# SCH_07_Output.net
KiCad netlist of a schematic drawn in Altium Designer
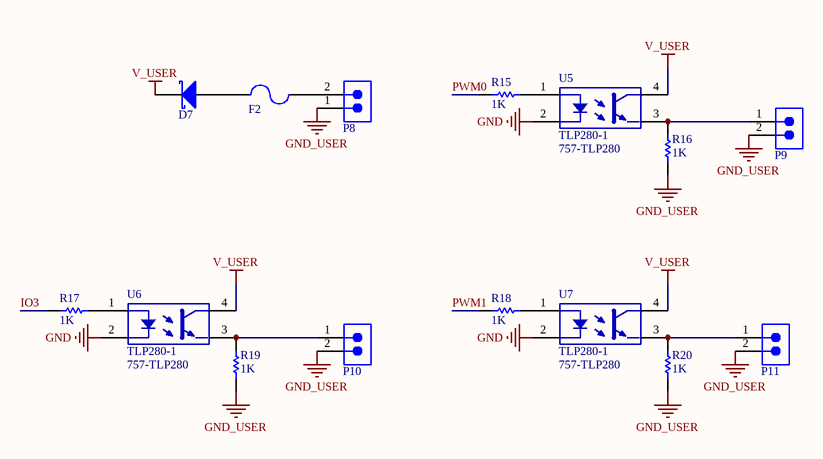
[diagram p0: SCH_07_Output.SchDoc]

(export (version "E")
  (design (tool "Eeschema 10.0.6"))
  (components
    (comp (ref "D7")
      (value "D Schottky")
      (footprint "SS34")
      (description "Schottky Diode")
      (fields (field (name "PUBLISHER") "Altium Limited"))
      (libsource (lib "PIF_Library") (part "D Schottky"))
    )
    (comp (ref "F2") (value "Fuse") (footprint "FUSE SMD") (libsource (lib "PIF_Library") (part "Fuse")))
    (comp (ref "P8")
      (value "691312510002")
      (footprint "691312510002")
      (description "WR-TBL Series 312 Open Horizontal PCB Header, THT, pitch 5.08mm, 2p")
      (fields (field (name "MANUFACTURER") "Wurth Elektronik"))
      (libsource (lib "Altium_WR-TBL (rev22b)") (part "691312510002"))
    )
    (comp (ref "P9")
      (value "691312510002")
      (footprint "691312510002")
      (description "WR-TBL Series 312 Open Horizontal PCB Header, THT, pitch 5.08mm, 2p")
      (fields (field (name "MANUFACTURER") "Wurth Elektronik"))
      (libsource (lib "Altium_WR-TBL (rev22b)") (part "691312510002"))
    )
    (comp (ref "P10")
      (value "691312510002")
      (footprint "691312510002")
      (description "WR-TBL Series 312 Open Horizontal PCB Header, THT, pitch 5.08mm, 2p")
      (fields (field (name "MANUFACTURER") "Wurth Elektronik"))
      (libsource (lib "Altium_WR-TBL (rev22b)") (part "691312510002"))
    )
    (comp (ref "P11")
      (value "691312510002")
      (footprint "691312510002")
      (description "WR-TBL Series 312 Open Horizontal PCB Header, THT, pitch 5.08mm, 2p")
      (fields (field (name "MANUFACTURER") "Wurth Elektronik"))
      (libsource (lib "Altium_WR-TBL (rev22b)") (part "691312510002"))
    )
    (comp (ref "R15")
      (value "1K")
      (footprint "RES-SM-0603")
      (description "Resistor")
      (fields (field (name "Comment") "RESISTOR SMD"))
      (libsource (lib "PIF_Library") (part "RESISTOR SMD"))
    )
    (comp (ref "R16")
      (value "1K")
      (footprint "RES-SM-0603")
      (description "Resistor")
      (fields (field (name "Comment") "RESISTOR SMD"))
      (libsource (lib "PIF_Library") (part "RESISTOR SMD"))
    )
    (comp (ref "R17")
      (value "1K")
      (footprint "RES-SM-0603")
      (description "Resistor")
      (fields (field (name "Comment") "RESISTOR SMD"))
      (libsource (lib "PIF_Library") (part "RESISTOR SMD"))
    )
    (comp (ref "R18")
      (value "1K")
      (footprint "RES-SM-0603")
      (description "Resistor")
      (fields (field (name "Comment") "RESISTOR SMD"))
      (libsource (lib "PIF_Library") (part "RESISTOR SMD"))
    )
    (comp (ref "R19")
      (value "1K")
      (footprint "RES-SM-0603")
      (description "Resistor")
      (fields (field (name "Comment") "RESISTOR SMD"))
      (libsource (lib "PIF_Library") (part "RESISTOR SMD"))
    )
    (comp (ref "R20")
      (value "1K")
      (footprint "RES-SM-0603")
      (description "Resistor")
      (fields (field (name "Comment") "RESISTOR SMD"))
      (libsource (lib "PIF_Library") (part "RESISTOR SMD"))
    )
    (comp (ref "U5")
      (value "TLP280-1")
      (footprint "SOIC127P700X240-4N")
      (description "Transistor Output Optocouplers 80Vceo 2500Vrms AC input")
      (fields (field (name "SUPPLIER PART NUMBER 1") "757-TLP280"))
      (libsource (lib "Huy_Lib") (part "TLP280-1"))
    )
    (comp (ref "U6")
      (value "TLP280-1")
      (footprint "SOIC127P700X240-4N")
      (description "Transistor Output Optocouplers 80Vceo 2500Vrms AC input")
      (fields (field (name "SUPPLIER PART NUMBER 1") "757-TLP280"))
      (libsource (lib "Huy_Lib") (part "TLP280-1"))
    )
    (comp (ref "U7")
      (value "TLP280-1")
      (footprint "SOIC127P700X240-4N")
      (description "Transistor Output Optocouplers 80Vceo 2500Vrms AC input")
      (fields (field (name "SUPPLIER PART NUMBER 1") "757-TLP280"))
      (libsource (lib "Huy_Lib") (part "TLP280-1"))
    )
  )
  (nets
    (net (code "1") (name "/IO3") (class "Default")
      (node (ref "R17") (pin "2") (pinfunction "2_2") (pintype "passive"))
    )
    (net (code "2") (name "/PWM0") (class "Default")
      (node (ref "R15") (pin "2") (pinfunction "2_2") (pintype "passive"))
    )
    (net (code "3") (name "/PWM1") (class "Default")
      (node (ref "R18") (pin "2") (pinfunction "2_2") (pintype "passive"))
    )
    (net (code "4") (name "GND") (class "Default")
      (node (ref "U5") (pin "2") (pinfunction "2_2") (pintype "passive"))
      (node (ref "U6") (pin "2") (pinfunction "2_2") (pintype "passive"))
      (node (ref "U7") (pin "2") (pinfunction "2_2") (pintype "passive"))
    )
    (net (code "5") (name "GND_USER") (class "Default")
      (node (ref "P10") (pin "2") (pinfunction "2_2") (pintype "passive"))
      (node (ref "P11") (pin "2") (pinfunction "2_2") (pintype "passive"))
      (node (ref "P8") (pin "1") (pinfunction "1_1") (pintype "passive"))
      (node (ref "P9") (pin "2") (pinfunction "2_2") (pintype "passive"))
      (node (ref "R16") (pin "1") (pinfunction "1_1") (pintype "passive"))
      (node (ref "R19") (pin "1") (pinfunction "1_1") (pintype "passive"))
      (node (ref "R20") (pin "1") (pinfunction "1_1") (pintype "passive"))
    )
    (net (code "6") (name "Net-(D7-A)") (class "Default")
      (node (ref "D7") (pin "1") (pinfunction "A_1") (pintype "passive"))
      (node (ref "F2") (pin "1") (pinfunction "1_1") (pintype "passive"))
    )
    (net (code "7") (name "Net-(F2-Pad2)") (class "Default")
      (node (ref "F2") (pin "2") (pinfunction "2_2") (pintype "passive"))
      (node (ref "P8") (pin "2") (pinfunction "2_2") (pintype "passive"))
    )
    (net (code "8") (name "Net-(P9-Pad1)") (class "Default")
      (node (ref "P9") (pin "1") (pinfunction "1_1") (pintype "passive"))
      (node (ref "R16") (pin "2") (pinfunction "2_2") (pintype "passive"))
      (node (ref "U5") (pin "3") (pinfunction "3_3") (pintype "passive"))
    )
    (net (code "9") (name "Net-(P10-Pad1)") (class "Default")
      (node (ref "P10") (pin "1") (pinfunction "1_1") (pintype "passive"))
      (node (ref "R19") (pin "2") (pinfunction "2_2") (pintype "passive"))
      (node (ref "U6") (pin "3") (pinfunction "3_3") (pintype "passive"))
    )
    (net (code "10") (name "Net-(P11-Pad1)") (class "Default")
      (node (ref "P11") (pin "1") (pinfunction "1_1") (pintype "passive"))
      (node (ref "R20") (pin "2") (pinfunction "2_2") (pintype "passive"))
      (node (ref "U7") (pin "3") (pinfunction "3_3") (pintype "passive"))
    )
    (net (code "11") (name "Net-(R15-Pad1)") (class "Default")
      (node (ref "R15") (pin "1") (pinfunction "1_1") (pintype "passive"))
      (node (ref "U5") (pin "1") (pinfunction "1_1") (pintype "passive"))
    )
    (net (code "12") (name "Net-(R17-Pad1)") (class "Default")
      (node (ref "R17") (pin "1") (pinfunction "1_1") (pintype "passive"))
      (node (ref "U6") (pin "1") (pinfunction "1_1") (pintype "passive"))
    )
    (net (code "13") (name "Net-(R18-Pad1)") (class "Default")
      (node (ref "R18") (pin "1") (pinfunction "1_1") (pintype "passive"))
      (node (ref "U7") (pin "1") (pinfunction "1_1") (pintype "passive"))
    )
    (net (code "14") (name "V_USER") (class "Default")
      (node (ref "D7") (pin "2") (pinfunction "K_2") (pintype "passive"))
      (node (ref "U5") (pin "4") (pinfunction "4_4") (pintype "passive"))
      (node (ref "U6") (pin "4") (pinfunction "4_4") (pintype "passive"))
      (node (ref "U7") (pin "4") (pinfunction "4_4") (pintype "passive"))
    )
  )
)
